# T14_SuperDuperRev3.net
KiCad netlist of a schematic drawn in EAGLE
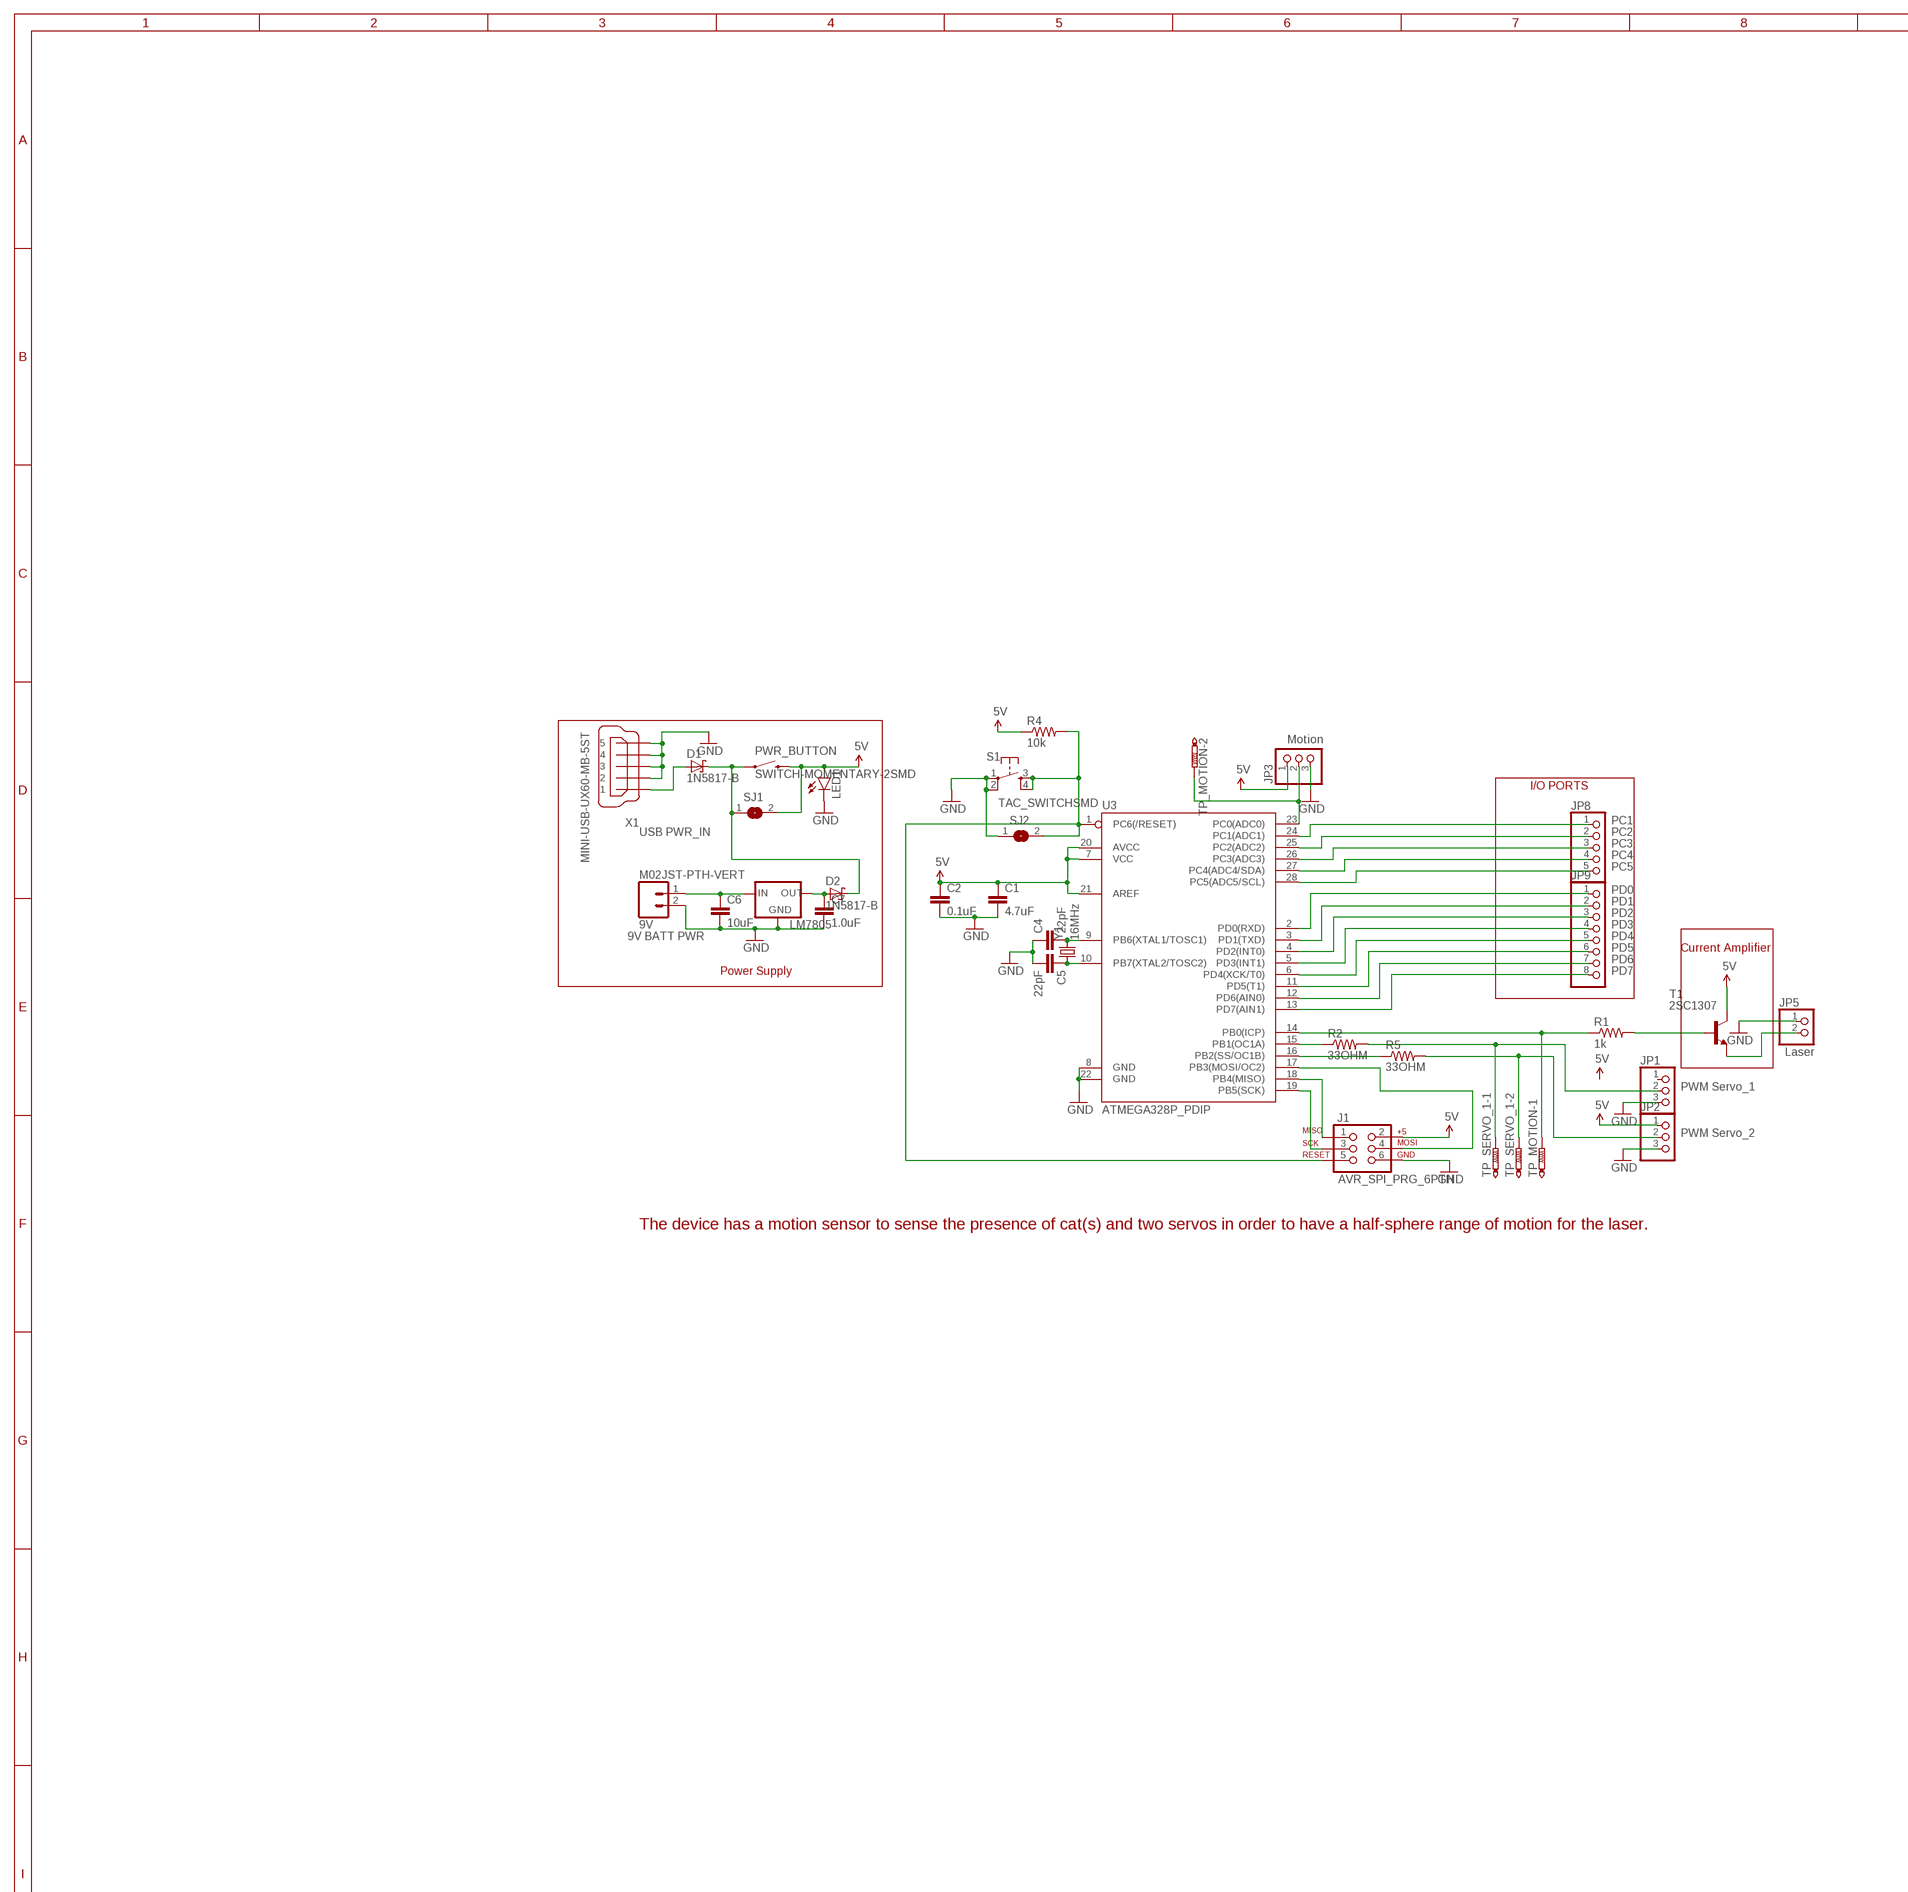
[diagram p0: schematic, sheet 1, part 1 of 2]
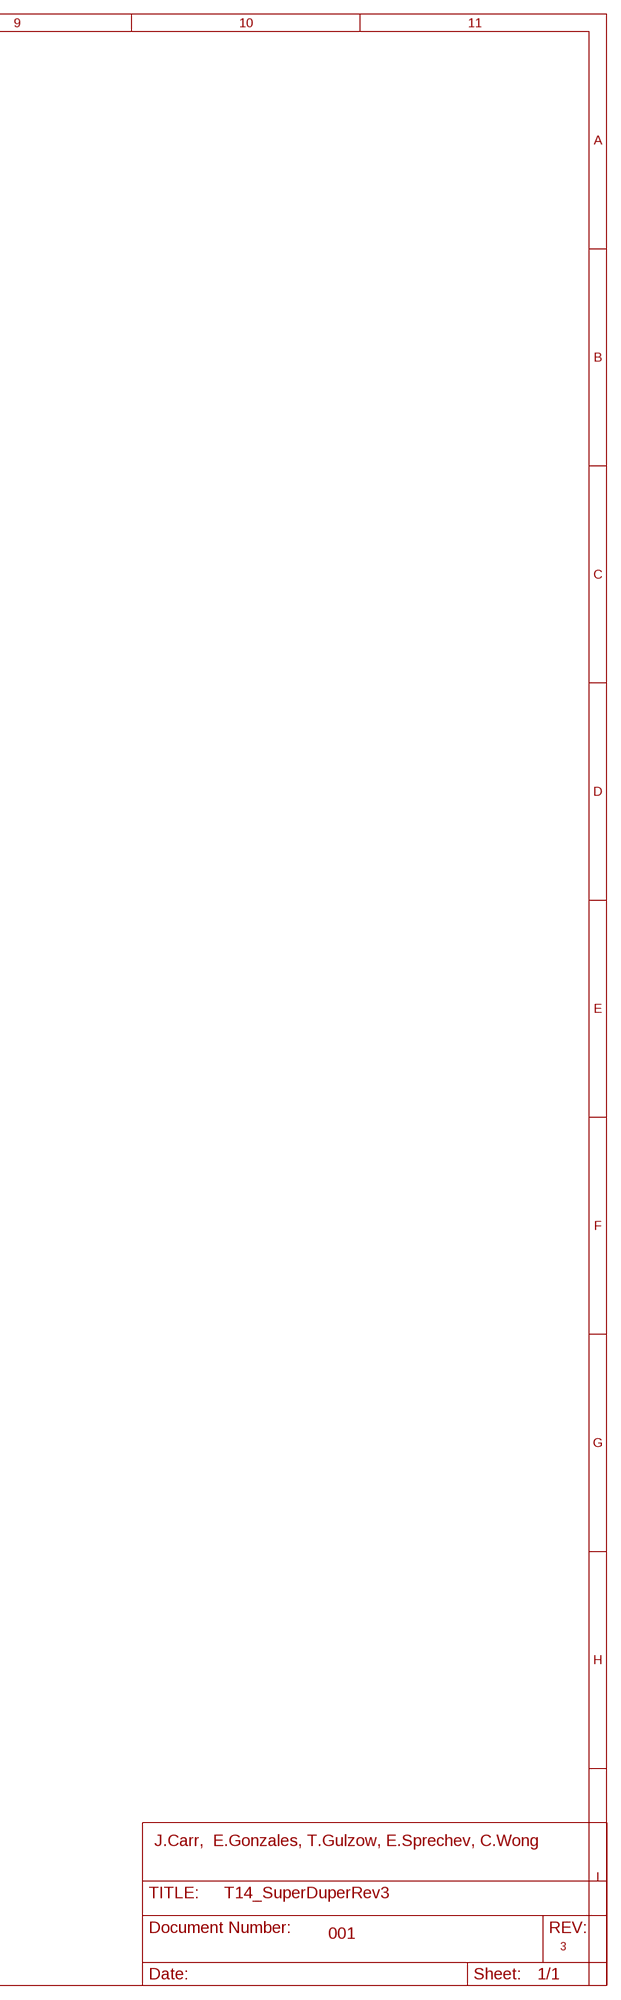
[diagram p1: schematic, sheet 1, part 2 of 2]

(export (version "E")
  (design (tool "Eeschema 10.0.6"))
  (components
    (comp (ref "9V")
      (value "M02JST-PTH-VERT")
      (footprint "eagle-import:JST-2-PTH-VERT")
      (libsource (lib "eagle-import") (part "M02JST-PTH-VERT"))
    )
    (comp (ref "C1")
      (value "4.7uF")
      (footprint "eagle-import:0603-CAP")
      (libsource (lib "eagle-import") (part "4.7UF-6.3V-10%(0603)0603"))
    )
    (comp (ref "C2")
      (value "0.1uF")
      (footprint "eagle-import:0603-CAP")
      (libsource (lib "eagle-import") (part "0.1UF-25V(+80/-20%)(0603)"))
    )
    (comp (ref "C4")
      (value "22pF")
      (footprint "eagle-import:0603-CAP")
      (libsource (lib "eagle-import") (part "4.7UF-6.3V-10%(0603)0603"))
    )
    (comp (ref "C5")
      (value "22pF")
      (footprint "eagle-import:0603-CAP")
      (libsource (lib "eagle-import") (part "4.7UF-6.3V-10%(0603)0603"))
    )
    (comp (ref "C6")
      (value "10uF")
      (footprint "eagle-import:0402-CAP")
      (libsource (lib "eagle-import") (part "1.0UF-16V-10%(0402)"))
    )
    (comp (ref "C7")
      (value "1.0uF")
      (footprint "eagle-import:0402-CAP")
      (libsource (lib "eagle-import") (part "1.0UF-16V-10%(0402)"))
    )
    (comp (ref "D1")
      (value "1N5817-B")
      (footprint "eagle-import:DO41-7.6")
      (libsource (lib "eagle-import") (part "1N5817-B"))
    )
    (comp (ref "D2")
      (value "1N5817-B")
      (footprint "eagle-import:DO41-7.6")
      (libsource (lib "eagle-import") (part "1N5817-B"))
    )
    (comp (ref "J1")
      (value "AVR_SPI_PRG_6PTH")
      (footprint "eagle-import:2X3")
      (libsource (lib "eagle-import") (part "AVR_SPI_PRG_6PTH"))
    )
    (comp (ref "JP1")
      (value "PINHD-1X3")
      (footprint "eagle-import:1X03")
      (libsource (lib "eagle-import") (part "PINHD-1X3"))
    )
    (comp (ref "JP2")
      (value "PINHD-1X3")
      (footprint "eagle-import:1X03")
      (libsource (lib "eagle-import") (part "PINHD-1X3"))
    )
    (comp (ref "JP3")
      (value "PINHD-1X3")
      (footprint "eagle-import:1X03")
      (libsource (lib "eagle-import") (part "PINHD-1X3"))
    )
    (comp (ref "JP5")
      (value "PINHD-1X2")
      (footprint "eagle-import:1X02")
      (libsource (lib "eagle-import") (part "PINHD-1X2"))
    )
    (comp (ref "JP8")
      (value "PINHD-1X5")
      (footprint "eagle-import:1X05")
      (libsource (lib "eagle-import") (part "PINHD-1X5"))
    )
    (comp (ref "JP9")
      (value "PINHD-1X8")
      (footprint "eagle-import:1X08")
      (libsource (lib "eagle-import") (part "PINHD-1X8"))
    )
    (comp (ref "LED1")
      (value "LED-3MM-NO_SILK")
      (footprint "eagle-import:LED3MM-NS")
      (libsource (lib "eagle-import") (part "LED-3MM-NO_SILK"))
    )
    (comp (ref "LM7805")
      (value "V_REG_78XXSIDE")
      (footprint "eagle-import:78XXL")
      (libsource (lib "eagle-import") (part "V_REG_78XXSIDE"))
    )
    (comp (ref "PWR_BUTTON")
      (value "SWITCH-MOMENTARY-2SMD")
      (footprint "eagle-import:TACTILE-SWITCH-SMD")
      (libsource (lib "eagle-import") (part "SWITCH-MOMENTARY-2SMD"))
    )
    (comp (ref "R1")
      (value "1k")
      (footprint "eagle-import:0603")
      (libsource (lib "eagle-import") (part "33OHM1/10W1%(0603)"))
    )
    (comp (ref "R2")
      (value "33OHM")
      (footprint "eagle-import:0603")
      (libsource (lib "eagle-import") (part "33OHM1/10W1%(0603)"))
    )
    (comp (ref "R4")
      (value "10k")
      (footprint "eagle-import:0603")
      (libsource (lib "eagle-import") (part "33OHM1/10W1%(0603)"))
    )
    (comp (ref "R5")
      (value "33OHM")
      (footprint "eagle-import:0603")
      (libsource (lib "eagle-import") (part "33OHM1/10W1%(0603)"))
    )
    (comp (ref "S1")
      (value "TAC_SWITCHSMD")
      (footprint "eagle-import:TACTILE-SWITCH-SMD")
      (libsource (lib "eagle-import") (part "TAC_SWITCHSMD"))
    )
    (comp (ref "SJ1") (value "SJ") (footprint "eagle-import:SJ") (libsource (lib "eagle-import") (part "SJ")))
    (comp (ref "SJ2") (value "SJ") (footprint "eagle-import:SJ") (libsource (lib "eagle-import") (part "SJ")))
    (comp (ref "T1")
      (value "2SC1307")
      (footprint "eagle-import:TO220AV")
      (libsource (lib "eagle-import") (part "2SC1307"))
    )
    (comp (ref "TP_MOTION")
      (value "PTR2")
      (footprint "eagle-import:P2-38-17")
      (libsource (lib "eagle-import") (part "PTR2"))
    )
    (comp (ref "TP_SERVO_1")
      (value "PTR2")
      (footprint "eagle-import:P2-38-17")
      (libsource (lib "eagle-import") (part "PTR2"))
    )
    (comp (ref "U3")
      (value "ATMEGA328P_PDIP")
      (footprint "eagle-import:DIL28-3")
      (libsource (lib "eagle-import") (part "ATMEGA328P_PDIP"))
    )
    (comp (ref "X1")
      (value "MINI-USB-UX60-MB-5ST")
      (footprint "eagle-import:UX60-MB-5ST")
      (libsource (lib "eagle-import") (part "MINI-USB-UX60-MB-5ST"))
    )
    (comp (ref "Y1")
      (value "16MHz")
      (footprint "eagle-import:CRYSTAL-SMD-10.5X4.8-2PIN")
      (libsource (lib "eagle-import") (part "CRYSTAL10.5X4.8"))
    )
  )
  (nets
    (net (code "1") (name "5V") (class "Default")
      (node (ref "C1") (pin "1") (pinfunction "1_1") (pintype "passive"))
      (node (ref "C2") (pin "1") (pinfunction "1_1") (pintype "passive"))
      (node (ref "J1") (pin "2") (pinfunction "2_2") (pintype "passive"))
      (node (ref "JP2") (pin "1") (pinfunction "1_1") (pintype "passive"))
      (node (ref "JP3") (pin "1") (pinfunction "1_1") (pintype "passive"))
      (node (ref "LED1") (pin "A") (pinfunction "A_A") (pintype "passive"))
      (node (ref "PWR_BUTTON") (pin "3") (pinfunction "2_3") (pintype "passive"))
      (node (ref "R4") (pin "1") (pinfunction "1_1") (pintype "passive"))
      (node (ref "SJ1") (pin "2") (pinfunction "2_2") (pintype "passive"))
      (node (ref "T1") (pin "2") (pinfunction "C_2") (pintype "passive"))
      (node (ref "U3") (pin "20") (pinfunction "AVCC_20") (pintype "bidirectional"))
      (node (ref "U3") (pin "21") (pinfunction "AREF_21") (pintype "bidirectional"))
      (node (ref "U3") (pin "7") (pinfunction "VCC_7") (pintype "bidirectional"))
    )
    (net (code "2") (name "GND") (class "Default")
      (node (ref "9V") (pin "2") (pinfunction "2_2") (pintype "passive"))
      (node (ref "C1") (pin "2") (pinfunction "2_2") (pintype "passive"))
      (node (ref "C2") (pin "2") (pinfunction "2_2") (pintype "passive"))
      (node (ref "C4") (pin "1") (pinfunction "1_1") (pintype "passive"))
      (node (ref "C5") (pin "2") (pinfunction "2_2") (pintype "passive"))
      (node (ref "C6") (pin "2") (pinfunction "2_2") (pintype "passive"))
      (node (ref "C7") (pin "2") (pinfunction "2_2") (pintype "passive"))
      (node (ref "J1") (pin "6") (pinfunction "6_6") (pintype "passive"))
      (node (ref "JP1") (pin "3") (pinfunction "3_3") (pintype "passive"))
      (node (ref "JP2") (pin "3") (pinfunction "3_3") (pintype "passive"))
      (node (ref "JP3") (pin "3") (pinfunction "3_3") (pintype "passive"))
      (node (ref "JP5") (pin "1") (pinfunction "1_1") (pintype "passive"))
      (node (ref "LED1") (pin "K") (pinfunction "C_K") (pintype "passive"))
      (node (ref "LM7805") (pin "GND") (pinfunction "GND_GND") (pintype "input"))
      (node (ref "S1") (pin "1") (pinfunction "1_1") (pintype "passive"))
      (node (ref "S1") (pin "2") (pinfunction "2_2") (pintype "passive"))
      (node (ref "SJ2") (pin "1") (pinfunction "1_1") (pintype "passive"))
      (node (ref "U3") (pin "22") (pinfunction "GND_22") (pintype "bidirectional"))
      (node (ref "U3") (pin "8") (pinfunction "GND_8") (pintype "bidirectional"))
      (node (ref "X1") (pin "2") (pinfunction "2_2") (pintype "input"))
      (node (ref "X1") (pin "3") (pinfunction "3_3") (pintype "input"))
      (node (ref "X1") (pin "4") (pinfunction "4_4") (pintype "input"))
      (node (ref "X1") (pin "5") (pinfunction "5_5") (pintype "input"))
    )
    (net (code "3") (name "Net-(9V-Pad1)") (class "Default")
      (node (ref "9V") (pin "1") (pinfunction "1_1") (pintype "passive"))
      (node (ref "C6") (pin "1") (pinfunction "1_1") (pintype "passive"))
      (node (ref "LM7805") (pin "IN") (pinfunction "IN_IN") (pintype "input"))
    )
    (net (code "4") (name "Net-(C7-Pad1)") (class "Default")
      (node (ref "C7") (pin "1") (pinfunction "1_1") (pintype "passive"))
      (node (ref "D2") (pin "A") (pinfunction "A_A") (pintype "passive"))
      (node (ref "LM7805") (pin "OUT") (pinfunction "OUT_OUT") (pintype "output"))
    )
    (net (code "5") (name "Net-(D1-PadA)") (class "Default")
      (node (ref "D1") (pin "A") (pinfunction "A_A") (pintype "passive"))
      (node (ref "X1") (pin "1") (pinfunction "1_1") (pintype "input"))
    )
    (net (code "6") (name "Net-(D1-PadC)") (class "Default")
      (node (ref "D1") (pin "C") (pinfunction "C_C") (pintype "passive"))
      (node (ref "D2") (pin "C") (pinfunction "C_C") (pintype "passive"))
      (node (ref "PWR_BUTTON") (pin "1") (pinfunction "1_1") (pintype "passive"))
      (node (ref "SJ1") (pin "1") (pinfunction "1_1") (pintype "passive"))
    )
    (net (code "7") (name "Net-(T1-B)") (class "Default")
      (node (ref "R1") (pin "2") (pinfunction "2_2") (pintype "passive"))
      (node (ref "T1") (pin "1") (pinfunction "B_1") (pintype "passive"))
    )
    (net (code "8") (name "Net-(T1-E)") (class "Default")
      (node (ref "JP5") (pin "2") (pinfunction "2_2") (pintype "passive"))
      (node (ref "T1") (pin "3") (pinfunction "E_3") (pintype "passive"))
    )
    (net (code "9") (name "Net-(TP_MOTIONA-TP)") (class "Default")
      (node (ref "R1") (pin "1") (pinfunction "1_1") (pintype "passive"))
      (node (ref "TP_MOTION") (pin "TP-1") (pinfunction "TP_TP-1") (pintype "input"))
      (node (ref "U3") (pin "14") (pinfunction "PB0(ICP)_14") (pintype "bidirectional"))
    )
    (net (code "10") (name "Net-(TP_MOTIONB-TP)") (class "Default")
      (node (ref "JP3") (pin "2") (pinfunction "2_2") (pintype "passive"))
      (node (ref "TP_MOTION") (pin "TP-2") (pinfunction "TP_TP-2") (pintype "input"))
      (node (ref "U3") (pin "23") (pinfunction "PC0(ADC0)_23") (pintype "bidirectional"))
    )
    (net (code "11") (name "Net-(TP_SERVO_1A-TP)") (class "Default")
      (node (ref "JP1") (pin "2") (pinfunction "2_2") (pintype "passive"))
      (node (ref "R2") (pin "2") (pinfunction "2_2") (pintype "passive"))
      (node (ref "TP_SERVO_1") (pin "TP-1") (pinfunction "TP_TP-1") (pintype "input"))
    )
    (net (code "12") (name "Net-(TP_SERVO_1B-TP)") (class "Default")
      (node (ref "JP2") (pin "2") (pinfunction "2_2") (pintype "passive"))
      (node (ref "R5") (pin "2") (pinfunction "2_2") (pintype "passive"))
      (node (ref "TP_SERVO_1") (pin "TP-2") (pinfunction "TP_TP-2") (pintype "input"))
    )
    (net (code "13") (name "Net-(U3-PB1(OC1A))") (class "Default")
      (node (ref "R2") (pin "1") (pinfunction "1_1") (pintype "passive"))
      (node (ref "U3") (pin "15") (pinfunction "PB1(OC1A)_15") (pintype "bidirectional"))
    )
    (net (code "14") (name "Net-(U3-PB2(SS{slash}OC1B))") (class "Default")
      (node (ref "R5") (pin "1") (pinfunction "1_1") (pintype "passive"))
      (node (ref "U3") (pin "16") (pinfunction "PB2(SS/OC1B)_16") (pintype "bidirectional"))
    )
    (net (code "15") (name "Net-(U3-PB3(MOSI{slash}OC2))") (class "Default")
      (node (ref "J1") (pin "4") (pinfunction "4_4") (pintype "passive"))
      (node (ref "U3") (pin "17") (pinfunction "PB3(MOSI/OC2)_17") (pintype "bidirectional"))
    )
    (net (code "16") (name "Net-(U3-PB4(MISO))") (class "Default")
      (node (ref "J1") (pin "1") (pinfunction "1_1") (pintype "passive"))
      (node (ref "U3") (pin "18") (pinfunction "PB4(MISO)_18") (pintype "bidirectional"))
    )
    (net (code "17") (name "Net-(U3-PB5(SCK))") (class "Default")
      (node (ref "J1") (pin "3") (pinfunction "3_3") (pintype "passive"))
      (node (ref "U3") (pin "19") (pinfunction "PB5(SCK)_19") (pintype "bidirectional"))
    )
    (net (code "18") (name "Net-(U3-PB6(XTAL1{slash}TOSC1))") (class "Default")
      (node (ref "C4") (pin "2") (pinfunction "2_2") (pintype "passive"))
      (node (ref "U3") (pin "9") (pinfunction "PB6(XTAL1/TOSC1)_9") (pintype "bidirectional"))
      (node (ref "Y1") (pin "P$2") (pinfunction "2_P$2") (pintype "passive"))
    )
    (net (code "19") (name "Net-(U3-PB7(XTAL2{slash}TOSC2))") (class "Default")
      (node (ref "C5") (pin "1") (pinfunction "1_1") (pintype "passive"))
      (node (ref "U3") (pin "10") (pinfunction "PB7(XTAL2/TOSC2)_10") (pintype "bidirectional"))
      (node (ref "Y1") (pin "P$1") (pinfunction "1_P$1") (pintype "passive"))
    )
    (net (code "20") (name "Net-(U3-PC1(ADC1))") (class "Default")
      (node (ref "JP8") (pin "1") (pinfunction "1_1") (pintype "passive"))
      (node (ref "U3") (pin "24") (pinfunction "PC1(ADC1)_24") (pintype "bidirectional"))
    )
    (net (code "21") (name "Net-(U3-PC2(ADC2))") (class "Default")
      (node (ref "JP8") (pin "2") (pinfunction "2_2") (pintype "passive"))
      (node (ref "U3") (pin "25") (pinfunction "PC2(ADC2)_25") (pintype "bidirectional"))
    )
    (net (code "22") (name "Net-(U3-PC3(ADC3))") (class "Default")
      (node (ref "JP8") (pin "3") (pinfunction "3_3") (pintype "passive"))
      (node (ref "U3") (pin "26") (pinfunction "PC3(ADC3)_26") (pintype "bidirectional"))
    )
    (net (code "23") (name "Net-(U3-PC4(ADC4{slash}SDA))") (class "Default")
      (node (ref "JP8") (pin "4") (pinfunction "4_4") (pintype "passive"))
      (node (ref "U3") (pin "27") (pinfunction "PC4(ADC4/SDA)_27") (pintype "bidirectional"))
    )
    (net (code "24") (name "Net-(U3-PC5(ADC5{slash}SCL))") (class "Default")
      (node (ref "JP8") (pin "5") (pinfunction "5_5") (pintype "passive"))
      (node (ref "U3") (pin "28") (pinfunction "PC5(ADC5/SCL)_28") (pintype "bidirectional"))
    )
    (net (code "25") (name "Net-(U3-PC6({slash}RESET))") (class "Default")
      (node (ref "J1") (pin "5") (pinfunction "5_5") (pintype "passive"))
      (node (ref "R4") (pin "2") (pinfunction "2_2") (pintype "passive"))
      (node (ref "S1") (pin "3") (pinfunction "3_3") (pintype "passive"))
      (node (ref "S1") (pin "4") (pinfunction "4_4") (pintype "passive"))
      (node (ref "SJ2") (pin "2") (pinfunction "2_2") (pintype "passive"))
      (node (ref "U3") (pin "1") (pinfunction "PC6(/RESET)_1") (pintype "bidirectional"))
    )
    (net (code "26") (name "Net-(U3-PD0(RXD))") (class "Default")
      (node (ref "JP9") (pin "1") (pinfunction "1_1") (pintype "passive"))
      (node (ref "U3") (pin "2") (pinfunction "PD0(RXD)_2") (pintype "bidirectional"))
    )
    (net (code "27") (name "Net-(U3-PD1(TXD))") (class "Default")
      (node (ref "JP9") (pin "2") (pinfunction "2_2") (pintype "passive"))
      (node (ref "U3") (pin "3") (pinfunction "PD1(TXD)_3") (pintype "bidirectional"))
    )
    (net (code "28") (name "Net-(U3-PD2(INT0))") (class "Default")
      (node (ref "JP9") (pin "3") (pinfunction "3_3") (pintype "passive"))
      (node (ref "U3") (pin "4") (pinfunction "PD2(INT0)_4") (pintype "bidirectional"))
    )
    (net (code "29") (name "Net-(U3-PD3(INT1))") (class "Default")
      (node (ref "JP9") (pin "4") (pinfunction "4_4") (pintype "passive"))
      (node (ref "U3") (pin "5") (pinfunction "PD3(INT1)_5") (pintype "bidirectional"))
    )
    (net (code "30") (name "Net-(U3-PD4(XCK{slash}T0))") (class "Default")
      (node (ref "JP9") (pin "5") (pinfunction "5_5") (pintype "passive"))
      (node (ref "U3") (pin "6") (pinfunction "PD4(XCK/T0)_6") (pintype "bidirectional"))
    )
    (net (code "31") (name "Net-(U3-PD5(T1))") (class "Default")
      (node (ref "JP9") (pin "6") (pinfunction "6_6") (pintype "passive"))
      (node (ref "U3") (pin "11") (pinfunction "PD5(T1)_11") (pintype "bidirectional"))
    )
    (net (code "32") (name "Net-(U3-PD6(AIN0))") (class "Default")
      (node (ref "JP9") (pin "7") (pinfunction "7_7") (pintype "passive"))
      (node (ref "U3") (pin "12") (pinfunction "PD6(AIN0)_12") (pintype "bidirectional"))
    )
    (net (code "33") (name "Net-(U3-PD7(AIN1))") (class "Default")
      (node (ref "JP9") (pin "8") (pinfunction "8_8") (pintype "passive"))
      (node (ref "U3") (pin "13") (pinfunction "PD7(AIN1)_13") (pintype "bidirectional"))
    )
    (net (code "34") (name "unconnected-(JP1-Pad1)") (class "Default")
      (node (ref "JP1") (pin "1") (pinfunction "1_1") (pintype "passive"))
    )
  )
)
